# schematic.net
KiCad netlist of a schematic drawn in EasyEDA
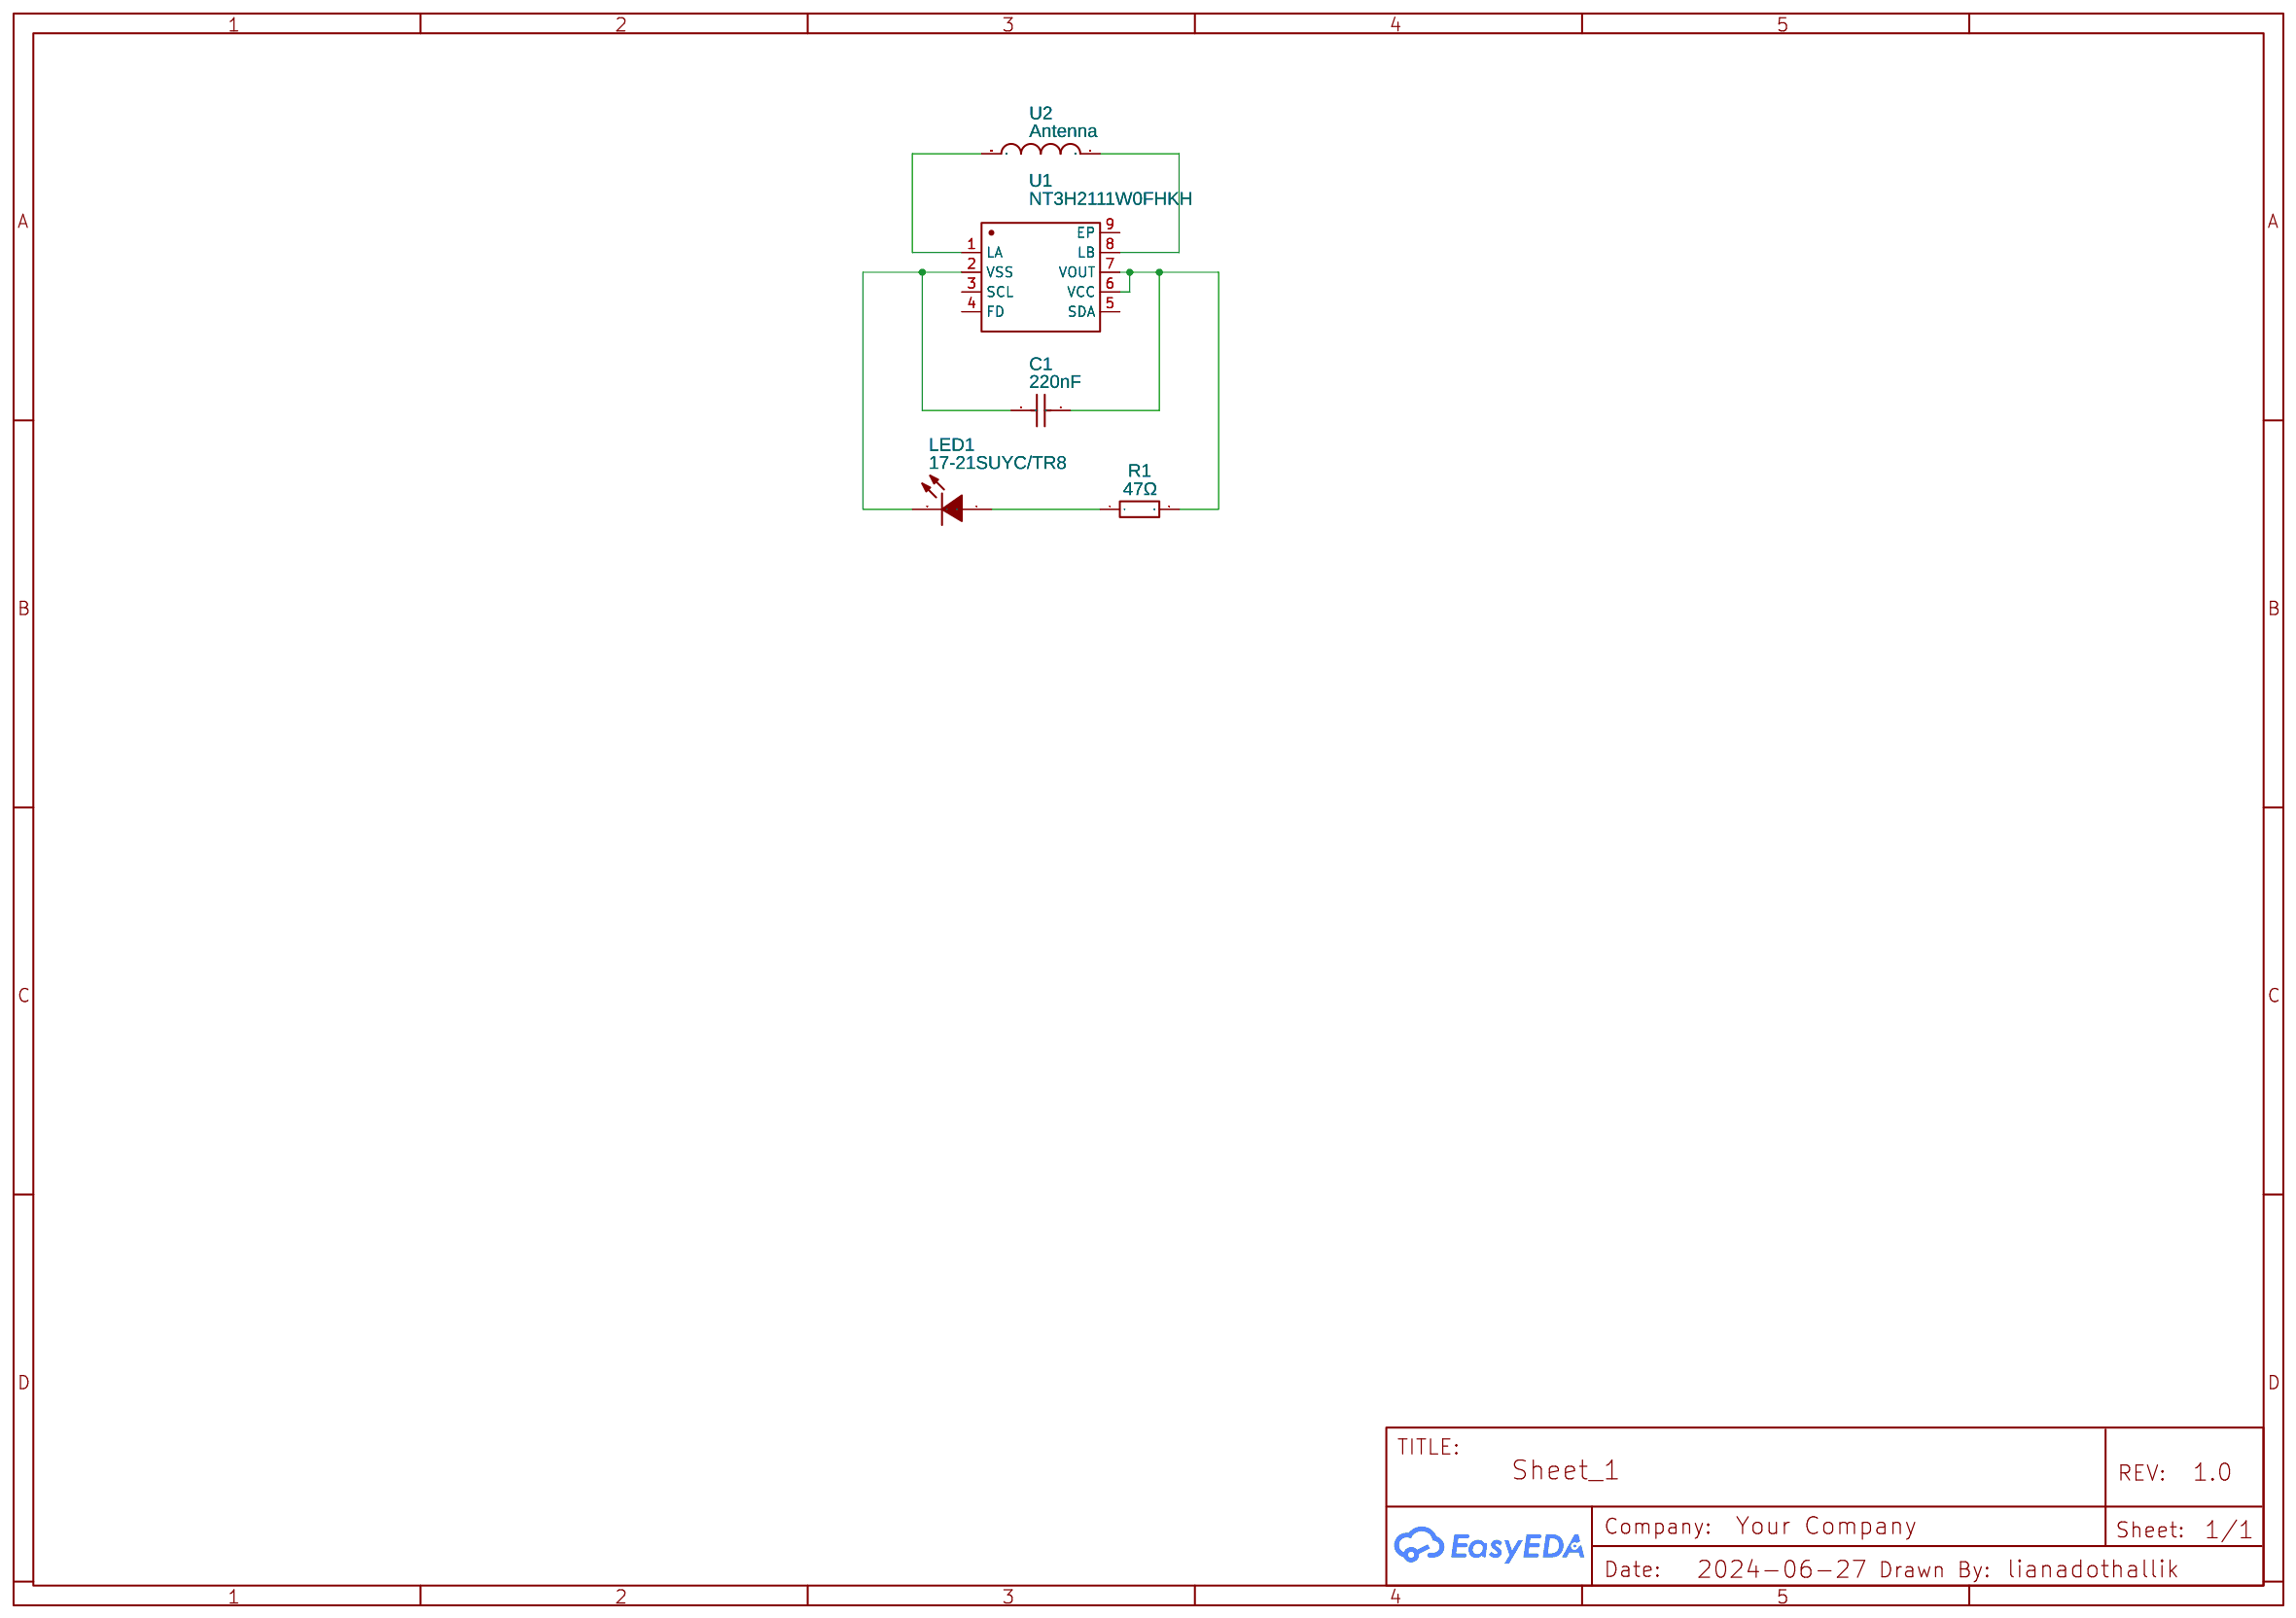
[diagram p0: schematic sheet]

(export (version "E")
  (design (tool "Eeschema 10.0.6"))
  (components
    (comp (ref "C1")
      (value "220nF")
      (fields
        (field (name "Manufacturer Part") "CL10B224KA8NNNC")
        (field (name "Manufacturer") "SAMSUNG(三星)")
      )
      (libsource (lib "") (part "CL10B224KA8NNNC"))
    )
    (comp (ref "LED1")
      (value "17-21SUYC/TR8")
      (fields (field (name "Manufacturer Part") "KT-0805黄灯") (field (name "Manufacturer") "KENTO"))
      (libsource (lib "") (part "17-21SUYC/TR8"))
    )
    (comp (ref "R1")
      (value "47Ω")
      (fields
        (field (name "Manufacturer Part") "0603WAF470JT5E")
        (field (name "Manufacturer") "UNI-ROYAL(厚声)")
      )
      (libsource (lib "") (part "0603WAF470JT5E"))
    )
    (comp (ref "U1")
      (value "NT3H2111W0FHKH")
      (fields (field (name "Manufacturer") "NXP(恩智浦)"))
      (libsource (lib "") (part "NT3H2111W0FHKH"))
    )
    (comp (ref "U2") (value "Antenna") (libsource (lib "") (part "Antenna")))
  )
  (nets
    (net (code "1") (name "Net-(LED1-+)") (class "Default")
      (node (ref "LED1") (pin "1") (pinfunction "+_1") (pintype "unspecified"))
      (node (ref "R1") (pin "1") (pinfunction "1_1") (pintype "input"))
    )
    (net (code "2") (name "Net-(LED1--)") (class "Default")
      (node (ref "C1") (pin "1") (pinfunction "1_1") (pintype "input"))
      (node (ref "LED1") (pin "2") (pinfunction "-_2") (pintype "unspecified"))
      (node (ref "U1") (pin "2") (pinfunction "VSS_2") (pintype "unspecified"))
    )
    (net (code "3") (name "Net-(U1-LA)") (class "Default")
      (node (ref "U1") (pin "1") (pinfunction "LA_1") (pintype "unspecified"))
      (node (ref "U2") (pin "P$2") (pinfunction "P$2_P$2") (pintype "unspecified"))
    )
    (net (code "4") (name "Net-(U1-LB)") (class "Default")
      (node (ref "U1") (pin "8") (pinfunction "LB_8") (pintype "unspecified"))
      (node (ref "U2") (pin "P$1") (pinfunction "P$1_P$1") (pintype "unspecified"))
    )
    (net (code "5") (name "Net-(U1-VCC)") (class "Default")
      (node (ref "C1") (pin "2") (pinfunction "2_2") (pintype "input"))
      (node (ref "R1") (pin "2") (pinfunction "2_2") (pintype "input"))
      (node (ref "U1") (pin "6") (pinfunction "VCC_6") (pintype "unspecified"))
      (node (ref "U1") (pin "7") (pinfunction "VOUT_7") (pintype "unspecified"))
    )
    (net (code "6") (name "unconnected-(U1-EP-Pad9)") (class "Default")
      (node (ref "U1") (pin "9") (pinfunction "EP_9") (pintype "unspecified"))
    )
    (net (code "7") (name "unconnected-(U1-FD-Pad4)") (class "Default")
      (node (ref "U1") (pin "4") (pinfunction "FD_4") (pintype "unspecified"))
    )
    (net (code "8") (name "unconnected-(U1-SCL-Pad3)") (class "Default")
      (node (ref "U1") (pin "3") (pinfunction "SCL_3") (pintype "unspecified"))
    )
    (net (code "9") (name "unconnected-(U1-SDA-Pad5)") (class "Default")
      (node (ref "U1") (pin "5") (pinfunction "SDA_5") (pintype "unspecified"))
    )
  )
)
